# LT3042_3V3.net
KiCad netlist of a schematic drawn in Altium Designer
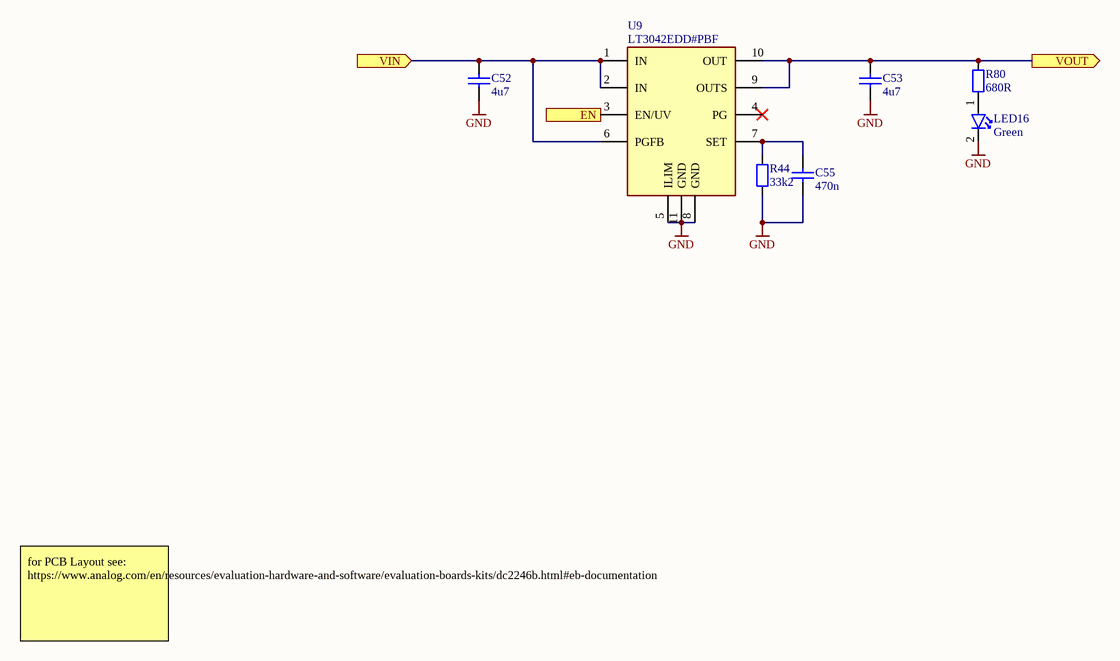
[diagram p0: LT3042_3V3.SchDoc]

(export (version "E")
  (design (tool "Eeschema 10.0.6"))
  (components
    (comp (ref "C52")
      (value "4u7")
      (footprint "C_1206_3216Metric_IPC_N")
      (description "Generic MLCC with 1206 Footprint")
      (libsource (lib "database_library") (part "Capacitor_unpol"))
    )
    (comp (ref "C53")
      (value "4u7")
      (footprint "C_1206_3216Metric_IPC_N")
      (description "Generic MLCC with 1206 Footprint")
      (libsource (lib "database_library") (part "Capacitor_unpol"))
    )
    (comp (ref "C55")
      (value "470n")
      (footprint "C_0402_1005Metric_IPC_N")
      (description "Generic MLCC with 0402 Footprint")
      (libsource (lib "database_library") (part "Capacitor_unpol"))
    )
    (comp (ref "LED16")
      (value "Green")
      (footprint "LED_0603_1806Metric_IPC_N")
      (description "MLCC, Low Current, Green, 2.2V, 20mA, 0603")
      (fields
        (field (name "MANUFACTURER") "Broadcom / Avago")
        (field (name "MANUFACTURER PART NUMBER") "HSMG-C190")
      )
      (libsource (lib "database_library") (part "LED"))
    )
    (comp (ref "R44")
      (value "33k2")
      (footprint "R_0402_1005Metric_IPC_N")
      (description "Generic Chip Resistor with 0402 Footprint")
      (libsource (lib "database_library") (part "Resistor"))
    )
    (comp (ref "R80")
      (value "680R")
      (footprint "R_0402_1005Metric_IPC_N")
      (description "Generic Chip Resistor with 0402 Footprint")
      (libsource (lib "database_library") (part "Resistor"))
    )
    (comp (ref "U9")
      (value "LT3042EDD#PBF")
      (footprint "DFN10_3x3")
      (fields (field (name "MANUFACTURER") "Analog Devices"))
      (libsource (lib "database_library") (part "LT3042-10"))
    )
  )
  (nets
    (net (code "1") (name "/EN") (class "Default")
      (node (ref "U9") (pin "3") (pinfunction "EN/UV_3") (pintype "passive"))
    )
    (net (code "2") (name "/VIN") (class "Default")
      (node (ref "C52") (pin "2") (pinfunction "2_2") (pintype "passive"))
      (node (ref "U9") (pin "1") (pinfunction "IN_1") (pintype "passive"))
      (node (ref "U9") (pin "2") (pinfunction "IN_2") (pintype "passive"))
      (node (ref "U9") (pin "6") (pinfunction "PGFB_6") (pintype "passive"))
    )
    (net (code "3") (name "/VOUT") (class "Default")
      (node (ref "C53") (pin "2") (pinfunction "2_2") (pintype "passive"))
      (node (ref "R80") (pin "1") (pinfunction "1_1") (pintype "passive"))
      (node (ref "U9") (pin "10") (pinfunction "OUT_10") (pintype "passive"))
      (node (ref "U9") (pin "9") (pinfunction "OUTS_9") (pintype "passive"))
    )
    (net (code "4") (name "GND") (class "Default")
      (node (ref "C52") (pin "1") (pinfunction "1_1") (pintype "passive"))
      (node (ref "C53") (pin "1") (pinfunction "1_1") (pintype "passive"))
      (node (ref "C55") (pin "1") (pinfunction "1_1") (pintype "passive"))
      (node (ref "LED16") (pin "2") (pinfunction "2_2") (pintype "passive"))
      (node (ref "R44") (pin "1") (pinfunction "1_1") (pintype "passive"))
      (node (ref "U9") (pin "11") (pinfunction "GND_11") (pintype "passive"))
      (node (ref "U9") (pin "5") (pinfunction "ILIM_5") (pintype "passive"))
      (node (ref "U9") (pin "8") (pinfunction "GND_8") (pintype "passive"))
    )
    (net (code "5") (name "Net-(LED16-Pad1)") (class "Default")
      (node (ref "LED16") (pin "1") (pinfunction "1_1") (pintype "passive"))
      (node (ref "R80") (pin "2") (pinfunction "2_2") (pintype "passive"))
    )
    (net (code "6") (name "Net-(U9-SET)") (class "Default")
      (node (ref "C55") (pin "2") (pinfunction "2_2") (pintype "passive"))
      (node (ref "R44") (pin "2") (pinfunction "2_2") (pintype "passive"))
      (node (ref "U9") (pin "7") (pinfunction "SET_7") (pintype "passive"))
    )
    (net (code "7") (name "unconnected-(U9-PG-Pad4)") (class "Default")
      (node (ref "U9") (pin "4") (pinfunction "PG_4") (pintype "passive+no_connect"))
    )
  )
)
